# MCU.net
KiCad netlist of a schematic drawn in Altium Designer
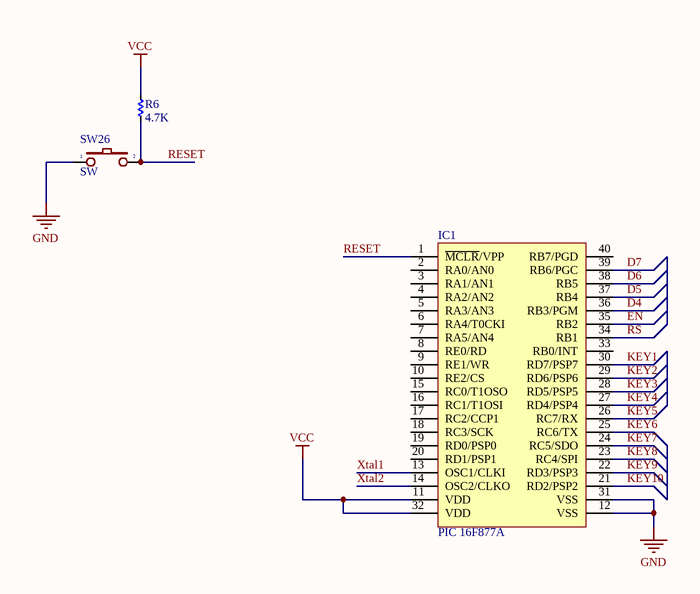
[diagram p0: MCU.SchDoc]

(export (version "E")
  (design (tool "Eeschema 10.0.6"))
  (components
    (comp (ref "IC1")
      (value "PIC 16F877A")
      (footprint "DIP40/W0.6")
      (description "8K FLASH, 368B RAM, 256B EFROM")
      (fields (field (name "COPYRIGHT BY") "VanDungEvn"))
      (libsource (lib "LIBRARY") (part "PIC16F877-PU"))
    )
    (comp (ref "R6")
      (value "4.7K")
      (footprint "RES-1/2W")
      (description "Res")
      (fields
        (field (name "MANUFACTURER") "Generic Components")
        (field (name "PUBLISHER") "Altium Hobart Technology Centre")
      )
      (libsource (lib "LIBRARY") (part "Res"))
    )
    (comp (ref "SW26")
      (value "SW")
      (footprint "SW-DIP1-1")
      (description "Switch button 2 pin")
      (libsource (lib "LIBRARY") (part "SW2"))
    )
  )
  (nets
    (net (code "1") (name "/D4") (class "Default")
      (node (ref "IC1") (pin "36") (pinfunction "RB3/PGM_36") (pintype "passive"))
    )
    (net (code "2") (name "/D5") (class "Default")
      (node (ref "IC1") (pin "37") (pinfunction "RB4_37") (pintype "passive"))
    )
    (net (code "3") (name "/D6") (class "Default")
      (node (ref "IC1") (pin "38") (pinfunction "RB5_38") (pintype "passive"))
    )
    (net (code "4") (name "/D7") (class "Default")
      (node (ref "IC1") (pin "39") (pinfunction "RB6/PGC_39") (pintype "passive"))
    )
    (net (code "5") (name "/EN") (class "Default")
      (node (ref "IC1") (pin "35") (pinfunction "RB2_35") (pintype "passive"))
    )
    (net (code "6") (name "/KEY1") (class "Default")
      (node (ref "IC1") (pin "30") (pinfunction "RD7/PSP7_30") (pintype "passive"))
    )
    (net (code "7") (name "/KEY2") (class "Default")
      (node (ref "IC1") (pin "29") (pinfunction "RD6/PSP6_29") (pintype "passive"))
    )
    (net (code "8") (name "/KEY3") (class "Default")
      (node (ref "IC1") (pin "28") (pinfunction "RD5/PSP5_28") (pintype "passive"))
    )
    (net (code "9") (name "/KEY4") (class "Default")
      (node (ref "IC1") (pin "27") (pinfunction "RD4/PSP4_27") (pintype "passive"))
    )
    (net (code "10") (name "/KEY5") (class "Default")
      (node (ref "IC1") (pin "26") (pinfunction "RC7/RX_26") (pintype "passive"))
    )
    (net (code "11") (name "/KEY6") (class "Default")
      (node (ref "IC1") (pin "25") (pinfunction "RC6/TX_25") (pintype "passive"))
    )
    (net (code "12") (name "/KEY7") (class "Default")
      (node (ref "IC1") (pin "24") (pinfunction "RC5/SDO_24") (pintype "passive"))
    )
    (net (code "13") (name "/KEY8") (class "Default")
      (node (ref "IC1") (pin "23") (pinfunction "RC4/SPI_23") (pintype "passive"))
    )
    (net (code "14") (name "/KEY9") (class "Default")
      (node (ref "IC1") (pin "22") (pinfunction "RD3/PSP3_22") (pintype "passive"))
    )
    (net (code "15") (name "/KEY10") (class "Default")
      (node (ref "IC1") (pin "21") (pinfunction "RD2/PSP2_21") (pintype "passive"))
    )
    (net (code "16") (name "/RESET") (class "Default")
      (node (ref "IC1") (pin "1") (pinfunction "~{MCLR}/VPP_1") (pintype "passive"))
      (node (ref "R6") (pin "2") (pinfunction "2_2") (pintype "passive"))
      (node (ref "SW26") (pin "2") (pinfunction "2_2") (pintype "passive"))
    )
    (net (code "17") (name "/RS") (class "Default")
      (node (ref "IC1") (pin "34") (pinfunction "RB1_34") (pintype "passive"))
    )
    (net (code "18") (name "/Xtal1") (class "Default")
      (node (ref "IC1") (pin "13") (pinfunction "OSC1/CLKI_13") (pintype "passive"))
    )
    (net (code "19") (name "/Xtal2") (class "Default")
      (node (ref "IC1") (pin "14") (pinfunction "OSC2/CLKO_14") (pintype "passive"))
    )
    (net (code "20") (name "GND") (class "Default")
      (node (ref "IC1") (pin "12") (pinfunction "VSS_12") (pintype "passive"))
      (node (ref "IC1") (pin "31") (pinfunction "VSS_31") (pintype "passive"))
      (node (ref "SW26") (pin "1") (pinfunction "1_1") (pintype "passive"))
    )
    (net (code "21") (name "VCC") (class "Default")
      (node (ref "IC1") (pin "11") (pinfunction "VDD_11") (pintype "passive"))
      (node (ref "IC1") (pin "32") (pinfunction "VDD_32") (pintype "passive"))
      (node (ref "R6") (pin "1") (pinfunction "1_1") (pintype "passive"))
    )
    (net (code "22") (name "unconnected-(IC1-RA0{slash}AN0-Pad2)") (class "Default")
      (node (ref "IC1") (pin "2") (pinfunction "RA0/AN0_2") (pintype "passive"))
    )
    (net (code "23") (name "unconnected-(IC1-RA1{slash}AN1-Pad3)") (class "Default")
      (node (ref "IC1") (pin "3") (pinfunction "RA1/AN1_3") (pintype "passive"))
    )
    (net (code "24") (name "unconnected-(IC1-RA2{slash}AN2-Pad4)") (class "Default")
      (node (ref "IC1") (pin "4") (pinfunction "RA2/AN2_4") (pintype "passive"))
    )
    (net (code "25") (name "unconnected-(IC1-RA3{slash}AN3-Pad5)") (class "Default")
      (node (ref "IC1") (pin "5") (pinfunction "RA3/AN3_5") (pintype "passive"))
    )
    (net (code "26") (name "unconnected-(IC1-RA4{slash}T0CKI-Pad6)") (class "Default")
      (node (ref "IC1") (pin "6") (pinfunction "RA4/T0CKI_6") (pintype "passive"))
    )
    (net (code "27") (name "unconnected-(IC1-RA5{slash}AN4-Pad7)") (class "Default")
      (node (ref "IC1") (pin "7") (pinfunction "RA5/AN4_7") (pintype "passive"))
    )
    (net (code "28") (name "unconnected-(IC1-RB0{slash}INT-Pad33)") (class "Default")
      (node (ref "IC1") (pin "33") (pinfunction "RB0/INT_33") (pintype "passive"))
    )
    (net (code "29") (name "unconnected-(IC1-RB7{slash}PGD-Pad40)") (class "Default")
      (node (ref "IC1") (pin "40") (pinfunction "RB7/PGD_40") (pintype "passive"))
    )
    (net (code "30") (name "unconnected-(IC1-RC0{slash}T1OSO-Pad15)") (class "Default")
      (node (ref "IC1") (pin "15") (pinfunction "RC0/T1OSO_15") (pintype "passive"))
    )
    (net (code "31") (name "unconnected-(IC1-RC1{slash}T1OSI-Pad16)") (class "Default")
      (node (ref "IC1") (pin "16") (pinfunction "RC1/T1OSI_16") (pintype "passive"))
    )
    (net (code "32") (name "unconnected-(IC1-RC2{slash}CCP1-Pad17)") (class "Default")
      (node (ref "IC1") (pin "17") (pinfunction "RC2/CCP1_17") (pintype "passive"))
    )
    (net (code "33") (name "unconnected-(IC1-RC3{slash}SCK-Pad18)") (class "Default")
      (node (ref "IC1") (pin "18") (pinfunction "RC3/SCK_18") (pintype "passive"))
    )
    (net (code "34") (name "unconnected-(IC1-RD0{slash}PSP0-Pad19)") (class "Default")
      (node (ref "IC1") (pin "19") (pinfunction "RD0/PSP0_19") (pintype "passive"))
    )
    (net (code "35") (name "unconnected-(IC1-RD1{slash}PSP1-Pad20)") (class "Default")
      (node (ref "IC1") (pin "20") (pinfunction "RD1/PSP1_20") (pintype "passive"))
    )
    (net (code "36") (name "unconnected-(IC1-RE0{slash}RD-Pad8)") (class "Default")
      (node (ref "IC1") (pin "8") (pinfunction "RE0/RD_8") (pintype "passive"))
    )
    (net (code "37") (name "unconnected-(IC1-RE1{slash}WR-Pad9)") (class "Default")
      (node (ref "IC1") (pin "9") (pinfunction "RE1/WR_9") (pintype "passive"))
    )
    (net (code "38") (name "unconnected-(IC1-RE2{slash}CS-Pad10)") (class "Default")
      (node (ref "IC1") (pin "10") (pinfunction "RE2/CS_10") (pintype "passive"))
    )
  )
)
